# I2C_and_UART.net
KiCad netlist of a schematic drawn in Altium Designer
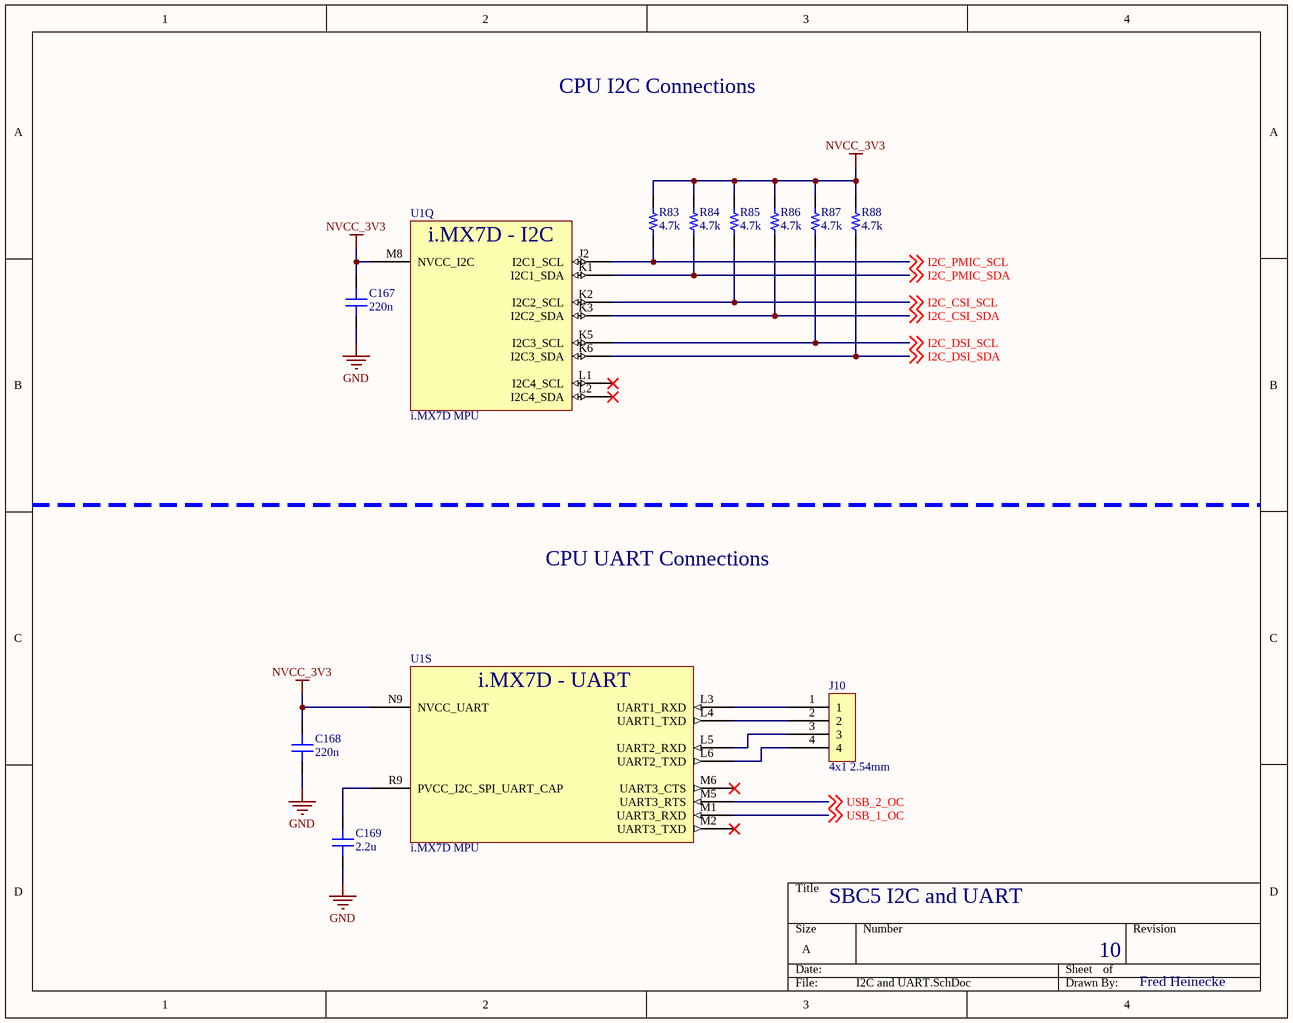
[diagram p0: I2C and UART.SchDoc]

(export (version "E")
  (design (tool "Eeschema 10.0.6"))
  (components
    (comp (ref "C167")
      (value "220n")
      (footprint "C0201")
      (description "Cap Ceramic Monolithic 0.22uF 16VDC 10% SMD Paper T/R")
      (fields
        (field (name "MANUFACTURER") "Murata")
        (field (name "MANUFACTURER PART NUMBER") "GRM033R61C224KE14D")
      )
      (libsource (lib "SBC5") (part "GRM033R61C224KE14D"))
    )
    (comp (ref "C168")
      (value "220n")
      (footprint "C0201")
      (description "Cap Ceramic Monolithic 0.22uF 16VDC 10% SMD Paper T/R")
      (fields
        (field (name "MANUFACTURER") "Murata")
        (field (name "MANUFACTURER PART NUMBER") "GRM033R61C224KE14D")
      )
      (libsource (lib "SBC5") (part "GRM033R61C224KE14D"))
    )
    (comp (ref "C169")
      (value "2.2u")
      (footprint "C0402")
      (description "TAIYO YUDEN         LMK105BJ225MV-F            CERAMIC CAPACITOR, 2.2UF, 10V, X5R, 20%, 0402")
      (fields
        (field (name "MANUFACTURER") "Taiyo Yuden")
        (field (name "MANUFACTURER PART NUMBER") "LMK105BJ225MV-F")
      )
      (libsource (lib "SBC5") (part "LMK105BJ225MV-F"))
    )
    (comp (ref "J10")
      (value "4x1 2.54mm")
      (footprint "PH1-04-UA")
      (description "Conn Unshrouded Header HDR 4 POS 2.54mm Solder ST Thru-Hole Bag")
      (fields
        (field (name "MANUFACTURER") "Adam Equipment")
        (field (name "MANUFACTURER PART NUMBER") "PH1-04-UA")
      )
      (libsource (lib "SBC5") (part "PH1-04-UA"))
    )
    (comp (ref "R83")
      (value "4.7k")
      (footprint "R0201")
      (description "GENERAL 0201 11% REEL (7INCH)")
      (fields
        (field (name "MANUFACTURER") "Yageo")
        (field (name "MANUFACTURER PART NUMBER") "RC0201FR-074K7L")
      )
      (libsource (lib "SBC5") (part "RC0201FR-074K7L"))
    )
    (comp (ref "R84")
      (value "4.7k")
      (footprint "R0201")
      (description "GENERAL 0201 11% REEL (7INCH)")
      (fields
        (field (name "MANUFACTURER") "Yageo")
        (field (name "MANUFACTURER PART NUMBER") "RC0201FR-074K7L")
      )
      (libsource (lib "SBC5") (part "RC0201FR-074K7L"))
    )
    (comp (ref "R85")
      (value "4.7k")
      (footprint "R0201")
      (description "GENERAL 0201 11% REEL (7INCH)")
      (fields
        (field (name "MANUFACTURER") "Yageo")
        (field (name "MANUFACTURER PART NUMBER") "RC0201FR-074K7L")
      )
      (libsource (lib "SBC5") (part "RC0201FR-074K7L"))
    )
    (comp (ref "R86")
      (value "4.7k")
      (footprint "R0201")
      (description "GENERAL 0201 11% REEL (7INCH)")
      (fields
        (field (name "MANUFACTURER") "Yageo")
        (field (name "MANUFACTURER PART NUMBER") "RC0201FR-074K7L")
      )
      (libsource (lib "SBC5") (part "RC0201FR-074K7L"))
    )
    (comp (ref "R87")
      (value "4.7k")
      (footprint "R0201")
      (description "GENERAL 0201 11% REEL (7INCH)")
      (fields
        (field (name "MANUFACTURER") "Yageo")
        (field (name "MANUFACTURER PART NUMBER") "RC0201FR-074K7L")
      )
      (libsource (lib "SBC5") (part "RC0201FR-074K7L"))
    )
    (comp (ref "R88")
      (value "4.7k")
      (footprint "R0201")
      (description "GENERAL 0201 11% REEL (7INCH)")
      (fields
        (field (name "MANUFACTURER") "Yageo")
        (field (name "MANUFACTURER PART NUMBER") "RC0201FR-074K7L")
      )
      (libsource (lib "SBC5") (part "RC0201FR-074K7L"))
    )
    (comp (ref "U1")
      (value "i.MX7D MPU")
      (footprint "BGA541C75P25X25_1900X1900X140")
      (description "Heterogeneous Multicore Processing Architecture")
      (fields
        (field (name "MANUFACTURER") "NXP Freescale")
        (field (name "MANUFACTURER PART NUMBER") "MCIMX7D2DVM12SD")
      )
      (libsource (lib "SBC5") (part "MCIMX7D2DVM12SD"))
    )
  )
  (nets
    (net (code "1") (name "GND") (class "Default")
      (node (ref "C167") (pin "1") (pinfunction "1_1") (pintype "passive"))
      (node (ref "C168") (pin "1") (pinfunction "1_1") (pintype "passive"))
      (node (ref "C169") (pin "1") (pinfunction "1_1") (pintype "passive"))
    )
    (net (code "2") (name "I2C_CSI_SCL") (class "Default")
      (node (ref "R85") (pin "1") (pinfunction "1_1") (pintype "passive"))
      (node (ref "U1") (pin "K2") (pinfunction "I2C2_SCL_K2") (pintype "bidirectional"))
    )
    (net (code "3") (name "I2C_CSI_SDA") (class "Default")
      (node (ref "R86") (pin "1") (pinfunction "1_1") (pintype "passive"))
      (node (ref "U1") (pin "K3") (pinfunction "I2C2_SDA_K3") (pintype "bidirectional"))
    )
    (net (code "4") (name "I2C_DSI_SCL") (class "Default")
      (node (ref "R87") (pin "1") (pinfunction "1_1") (pintype "passive"))
      (node (ref "U1") (pin "K5") (pinfunction "I2C3_SCL_K5") (pintype "bidirectional"))
    )
    (net (code "5") (name "I2C_DSI_SDA") (class "Default")
      (node (ref "R88") (pin "1") (pinfunction "1_1") (pintype "passive"))
      (node (ref "U1") (pin "K6") (pinfunction "I2C3_SDA_K6") (pintype "bidirectional"))
    )
    (net (code "6") (name "I2C_PMIC_SCL") (class "Default")
      (node (ref "R83") (pin "1") (pinfunction "1_1") (pintype "passive"))
      (node (ref "U1") (pin "J2") (pinfunction "I2C1_SCL_J2") (pintype "bidirectional"))
    )
    (net (code "7") (name "I2C_PMIC_SDA") (class "Default")
      (node (ref "R84") (pin "1") (pinfunction "1_1") (pintype "passive"))
      (node (ref "U1") (pin "K1") (pinfunction "I2C1_SDA_K1") (pintype "bidirectional"))
    )
    (net (code "8") (name "NVCC_3V3") (class "Default")
      (node (ref "C167") (pin "2") (pinfunction "2_2") (pintype "passive"))
      (node (ref "C168") (pin "2") (pinfunction "2_2") (pintype "passive"))
      (node (ref "R83") (pin "2") (pinfunction "2_2") (pintype "passive"))
      (node (ref "R84") (pin "2") (pinfunction "2_2") (pintype "passive"))
      (node (ref "R85") (pin "2") (pinfunction "2_2") (pintype "passive"))
      (node (ref "R86") (pin "2") (pinfunction "2_2") (pintype "passive"))
      (node (ref "R87") (pin "2") (pinfunction "2_2") (pintype "passive"))
      (node (ref "R88") (pin "2") (pinfunction "2_2") (pintype "passive"))
      (node (ref "U1") (pin "M8") (pinfunction "NVCC_I2C_M8") (pintype "power_in"))
      (node (ref "U1") (pin "N9") (pinfunction "NVCC_UART_N9") (pintype "power_in"))
    )
    (net (code "9") (name "Net-(U1S-PVCC_I2C_SPI_UART_CAP)") (class "Default")
      (node (ref "C169") (pin "2") (pinfunction "2_2") (pintype "passive"))
      (node (ref "U1") (pin "R9") (pinfunction "PVCC_I2C_SPI_UART_CAP_R9") (pintype "power_in"))
    )
    (net (code "10") (name "Net-(U1S-UART1_RXD)") (class "Default")
      (node (ref "J10") (pin "1") (pinfunction "1_1") (pintype "passive"))
      (node (ref "U1") (pin "L3") (pinfunction "UART1_RXD_L3") (pintype "input"))
    )
    (net (code "11") (name "Net-(U1S-UART1_TXD)") (class "Default")
      (node (ref "J10") (pin "2") (pinfunction "2_2") (pintype "passive"))
      (node (ref "U1") (pin "L4") (pinfunction "UART1_TXD_L4") (pintype "output"))
    )
    (net (code "12") (name "Net-(U1S-UART2_RXD)") (class "Default")
      (node (ref "J10") (pin "3") (pinfunction "3_3") (pintype "passive"))
      (node (ref "U1") (pin "L5") (pinfunction "UART2_RXD_L5") (pintype "input"))
    )
    (net (code "13") (name "Net-(U1S-UART2_TXD)") (class "Default")
      (node (ref "J10") (pin "4") (pinfunction "4_4") (pintype "passive"))
      (node (ref "U1") (pin "L6") (pinfunction "UART2_TXD_L6") (pintype "output"))
    )
    (net (code "14") (name "USB_1_OC") (class "Default")
      (node (ref "U1") (pin "M1") (pinfunction "UART3_RXD_M1") (pintype "input"))
    )
    (net (code "15") (name "USB_2_OC") (class "Default")
      (node (ref "U1") (pin "M5") (pinfunction "UART3_RTS_M5") (pintype "input"))
    )
    (net (code "16") (name "unconnected-(U1Q-I2C4_SCL-PadL1)") (class "Default")
      (node (ref "U1") (pin "L1") (pinfunction "I2C4_SCL_L1") (pintype "bidirectional+no_connect"))
    )
    (net (code "17") (name "unconnected-(U1Q-I2C4_SDA-PadL2)") (class "Default")
      (node (ref "U1") (pin "L2") (pinfunction "I2C4_SDA_L2") (pintype "bidirectional+no_connect"))
    )
    (net (code "18") (name "unconnected-(U1S-UART3_CTS-PadM6)") (class "Default")
      (node (ref "U1") (pin "M6") (pinfunction "UART3_CTS_M6") (pintype "output+no_connect"))
    )
    (net (code "19") (name "unconnected-(U1S-UART3_TXD-PadM2)") (class "Default")
      (node (ref "U1") (pin "M2") (pinfunction "UART3_TXD_M2") (pintype "output+no_connect"))
    )
  )
)
